# Diag64Cart.net
KiCad netlist of a schematic drawn in EAGLE
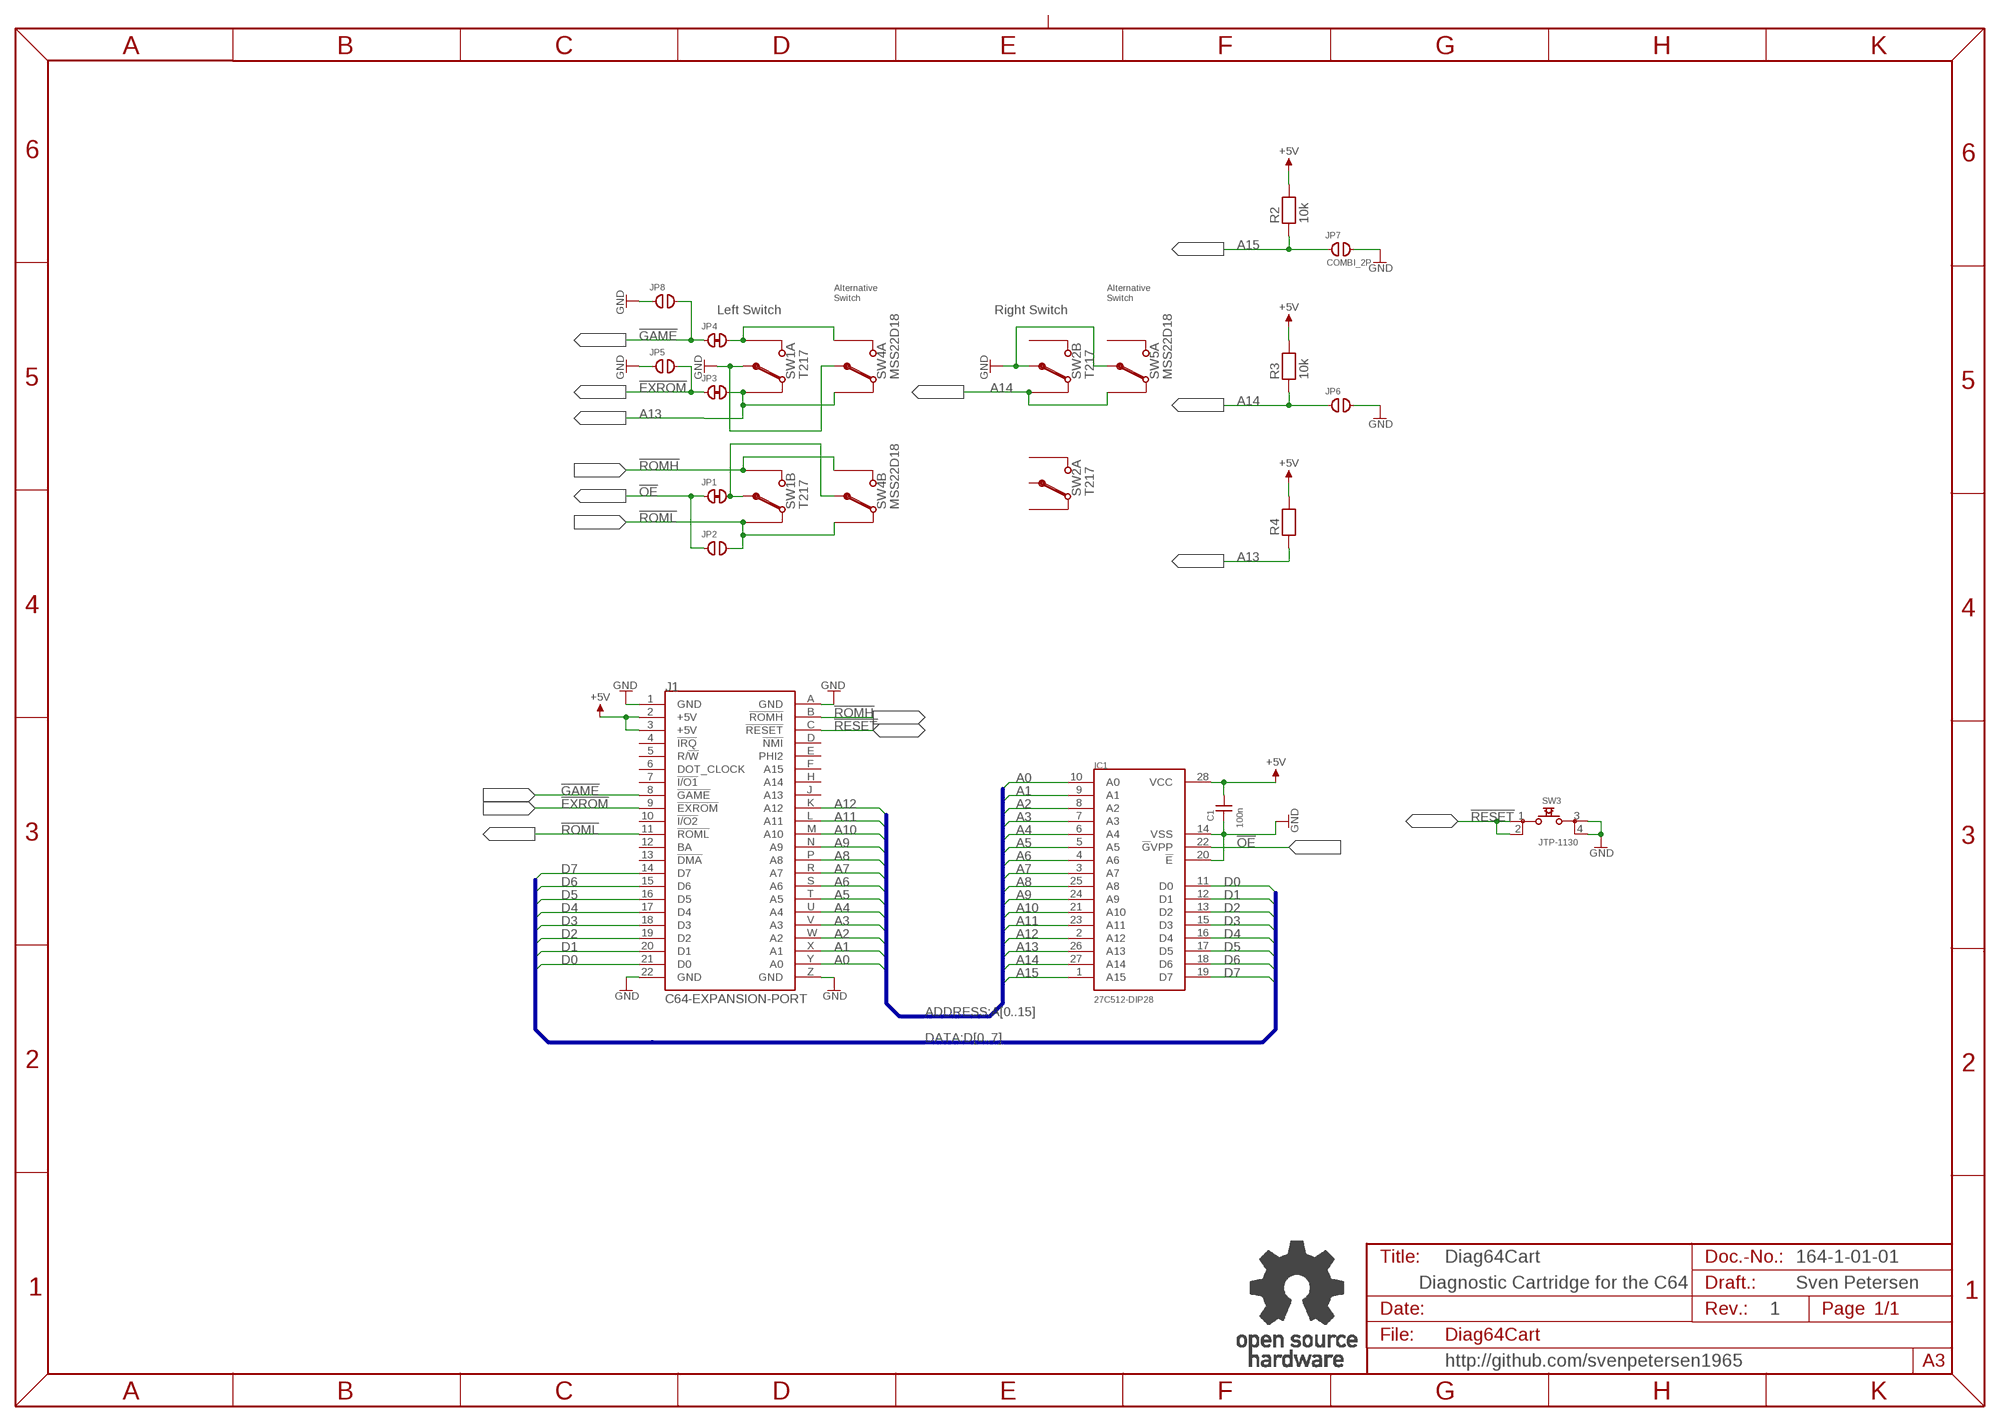
[diagram p0: schematic, sheet 1]

(export (version "E")
  (design (tool "Eeschema 10.0.6"))
  (components
    (comp (ref "C1")
      (value "100n")
      (footprint "eagle-import:C-2,5")
      (libsource (lib "eagle-import") (part "CAP01"))
    )
    (comp (ref "IC1")
      (value "27C512-DIP28")
      (footprint "eagle-import:DIL28-6")
      (libsource (lib "eagle-import") (part "M27C512-DIP28"))
    )
    (comp (ref "J1")
      (value "C64-EXPANSION-PORT")
      (footprint "eagle-import:EXPANSIO_SQ")
      (libsource (lib "eagle-import") (part "C64-EXPANSIONPNARROW"))
    )
    (comp (ref "JP1")
      (value "CLOSED")
      (footprint "eagle-import:CP_CL")
      (libsource (lib "eagle-import") (part "CLOSED"))
    )
    (comp (ref "JP2")
      (value "OPEN")
      (footprint "eagle-import:CP_OP")
      (libsource (lib "eagle-import") (part "OPEN"))
    )
    (comp (ref "JP3")
      (value "CLOSED")
      (footprint "eagle-import:CP_CL")
      (libsource (lib "eagle-import") (part "CLOSED"))
    )
    (comp (ref "JP4")
      (value "CLOSED")
      (footprint "eagle-import:CP_CL")
      (libsource (lib "eagle-import") (part "CLOSED"))
    )
    (comp (ref "JP5")
      (value "OPEN")
      (footprint "eagle-import:CP_OP")
      (libsource (lib "eagle-import") (part "OPEN"))
    )
    (comp (ref "JP6")
      (value "OPEN")
      (footprint "eagle-import:CP_OP")
      (libsource (lib "eagle-import") (part "OPEN"))
    )
    (comp (ref "JP7")
      (value "COMBI_2P")
      (footprint "eagle-import:COMBI-2P")
      (libsource (lib "eagle-import") (part "COMBI_2P"))
    )
    (comp (ref "JP8")
      (value "OPEN")
      (footprint "eagle-import:CP_OP")
      (libsource (lib "eagle-import") (part "OPEN"))
    )
    (comp (ref "R2")
      (value "10k")
      (footprint "eagle-import:R-10")
      (libsource (lib "eagle-import") (part "RES04"))
    )
    (comp (ref "R3")
      (value "10k")
      (footprint "eagle-import:R-10")
      (libsource (lib "eagle-import") (part "RES04"))
    )
    (comp (ref "R4")
      (value "10k")
      (footprint "eagle-import:R-10")
      (libsource (lib "eagle-import") (part "RES04"))
    )
    (comp (ref "SW1")
      (value "T217")
      (footprint "eagle-import:T217_SIDE")
      (libsource (lib "eagle-import") (part "T217"))
    )
    (comp (ref "SW2")
      (value "T217")
      (footprint "eagle-import:T217_SIDE")
      (libsource (lib "eagle-import") (part "T217"))
    )
    (comp (ref "SW3")
      (value "JTP-1130")
      (footprint "eagle-import:JTP-1130")
      (libsource (lib "eagle-import") (part "JTP-1130"))
    )
    (comp (ref "SW4")
      (value "MSS22D18")
      (footprint "eagle-import:DPDT_9MM")
      (libsource (lib "eagle-import") (part "DPDT_9MM"))
    )
    (comp (ref "SW5")
      (value "MSS22D18")
      (footprint "eagle-import:DPDT_9MM")
      (libsource (lib "eagle-import") (part "DPDT_9MM"))
    )
    (comp (ref "U$43")
      (value "OPEN_SOURCE_HW")
      (footprint "eagle-import:OPENHW")
      (libsource (lib "eagle-import") (part "OPEN_SOURCE_HW"))
    )
  )
  (nets
    (net (code "25") (name "+5V") (class "Default")
      (node (ref "C1") (pin "2") (pinfunction "2_2") (pintype "passive"))
      (node (ref "IC1") (pin "28") (pinfunction "VCC_28") (pintype "power_in"))
      (node (ref "J1") (pin "2") (pinfunction "+5V_2") (pintype "power_in"))
      (node (ref "J1") (pin "3") (pinfunction "+5V_3") (pintype "power_in"))
      (node (ref "R2") (pin "2") (pinfunction "2_2") (pintype "passive"))
      (node (ref "R3") (pin "2") (pinfunction "2_2") (pintype "passive"))
      (node (ref "R4") (pin "2") (pinfunction "2_2") (pintype "passive"))
    )
    (net (code "26") (name "/A0") (class "Default")
      (node (ref "IC1") (pin "10") (pinfunction "A0_10") (pintype "input"))
      (node (ref "J1") (pin "Y") (pinfunction "A0_Y") (pintype "bidirectional"))
    )
    (net (code "27") (name "/A1") (class "Default")
      (node (ref "IC1") (pin "9") (pinfunction "A1_9") (pintype "input"))
      (node (ref "J1") (pin "X") (pinfunction "A1_X") (pintype "bidirectional"))
    )
    (net (code "28") (name "/A2") (class "Default")
      (node (ref "IC1") (pin "8") (pinfunction "A2_8") (pintype "input"))
      (node (ref "J1") (pin "W") (pinfunction "A2_W") (pintype "bidirectional"))
    )
    (net (code "29") (name "/A3") (class "Default")
      (node (ref "IC1") (pin "7") (pinfunction "A3_7") (pintype "input"))
      (node (ref "J1") (pin "V") (pinfunction "A3_V") (pintype "bidirectional"))
    )
    (net (code "30") (name "/A4") (class "Default")
      (node (ref "IC1") (pin "6") (pinfunction "A4_6") (pintype "input"))
      (node (ref "J1") (pin "U") (pinfunction "A4_U") (pintype "bidirectional"))
    )
    (net (code "31") (name "/A5") (class "Default")
      (node (ref "IC1") (pin "5") (pinfunction "A5_5") (pintype "input"))
      (node (ref "J1") (pin "T") (pinfunction "A5_T") (pintype "bidirectional"))
    )
    (net (code "32") (name "/A6") (class "Default")
      (node (ref "IC1") (pin "4") (pinfunction "A6_4") (pintype "input"))
      (node (ref "J1") (pin "S") (pinfunction "A6_S") (pintype "bidirectional"))
    )
    (net (code "33") (name "/A7") (class "Default")
      (node (ref "IC1") (pin "3") (pinfunction "A7_3") (pintype "input"))
      (node (ref "J1") (pin "R") (pinfunction "A7_R") (pintype "bidirectional"))
    )
    (net (code "34") (name "/A8") (class "Default")
      (node (ref "IC1") (pin "25") (pinfunction "A8_25") (pintype "input"))
      (node (ref "J1") (pin "P") (pinfunction "A8_P") (pintype "bidirectional"))
    )
    (net (code "35") (name "/A9") (class "Default")
      (node (ref "IC1") (pin "24") (pinfunction "A9_24") (pintype "input"))
      (node (ref "J1") (pin "N") (pinfunction "A9_N") (pintype "bidirectional"))
    )
    (net (code "36") (name "/A10") (class "Default")
      (node (ref "IC1") (pin "21") (pinfunction "A10_21") (pintype "input"))
      (node (ref "J1") (pin "M") (pinfunction "A10_M") (pintype "bidirectional"))
    )
    (net (code "37") (name "/A11") (class "Default")
      (node (ref "IC1") (pin "23") (pinfunction "A11_23") (pintype "input"))
      (node (ref "J1") (pin "L") (pinfunction "A11_L") (pintype "bidirectional"))
    )
    (net (code "38") (name "/A12") (class "Default")
      (node (ref "IC1") (pin "2") (pinfunction "A12_2") (pintype "input"))
      (node (ref "J1") (pin "K") (pinfunction "A12_K") (pintype "bidirectional"))
    )
    (net (code "39") (name "/A13") (class "Default")
      (node (ref "IC1") (pin "26") (pinfunction "A13_26") (pintype "input"))
      (node (ref "JP3") (pin "2") (pinfunction "2_2") (pintype "passive"))
      (node (ref "R4") (pin "1") (pinfunction "1_1") (pintype "passive"))
      (node (ref "SW1") (pin "DWN1") (pinfunction "DWN_DWN1") (pintype "bidirectional"))
      (node (ref "SW4") (pin "3") (pinfunction "DWN_3") (pintype "bidirectional"))
    )
    (net (code "40") (name "/A14") (class "Default")
      (node (ref "IC1") (pin "27") (pinfunction "A14_27") (pintype "input"))
      (node (ref "JP6") (pin "1") (pinfunction "1_1") (pintype "passive"))
      (node (ref "R3") (pin "1") (pinfunction "1_1") (pintype "passive"))
      (node (ref "SW2") (pin "DWN2") (pinfunction "DWN_DWN2") (pintype "bidirectional"))
      (node (ref "SW5") (pin "3") (pinfunction "DWN_3") (pintype "bidirectional"))
    )
    (net (code "41") (name "/A15") (class "Default")
      (node (ref "IC1") (pin "1") (pinfunction "A15_1") (pintype "input"))
      (node (ref "JP7") (pin "1") (pinfunction "1_1") (pintype "passive"))
      (node (ref "R2") (pin "1") (pinfunction "1_1") (pintype "passive"))
    )
    (net (code "43") (name "/D0") (class "Default")
      (node (ref "IC1") (pin "11") (pinfunction "D0_11") (pintype "bidirectional"))
      (node (ref "J1") (pin "21") (pinfunction "D0_21") (pintype "bidirectional"))
    )
    (net (code "44") (name "/D1") (class "Default")
      (node (ref "IC1") (pin "12") (pinfunction "D1_12") (pintype "bidirectional"))
      (node (ref "J1") (pin "20") (pinfunction "D1_20") (pintype "bidirectional"))
    )
    (net (code "45") (name "/D2") (class "Default")
      (node (ref "IC1") (pin "13") (pinfunction "D2_13") (pintype "bidirectional"))
      (node (ref "J1") (pin "19") (pinfunction "D2_19") (pintype "bidirectional"))
    )
    (net (code "46") (name "/D3") (class "Default")
      (node (ref "IC1") (pin "15") (pinfunction "D3_15") (pintype "bidirectional"))
      (node (ref "J1") (pin "18") (pinfunction "D3_18") (pintype "bidirectional"))
    )
    (net (code "47") (name "/D4") (class "Default")
      (node (ref "IC1") (pin "16") (pinfunction "D4_16") (pintype "bidirectional"))
      (node (ref "J1") (pin "17") (pinfunction "D4_17") (pintype "bidirectional"))
    )
    (net (code "48") (name "/D5") (class "Default")
      (node (ref "IC1") (pin "17") (pinfunction "D5_17") (pintype "bidirectional"))
      (node (ref "J1") (pin "16") (pinfunction "D5_16") (pintype "bidirectional"))
    )
    (net (code "49") (name "/D6") (class "Default")
      (node (ref "IC1") (pin "18") (pinfunction "D6_18") (pintype "bidirectional"))
      (node (ref "J1") (pin "15") (pinfunction "D6_15") (pintype "bidirectional"))
    )
    (net (code "50") (name "/D7") (class "Default")
      (node (ref "IC1") (pin "19") (pinfunction "D7_19") (pintype "bidirectional"))
      (node (ref "J1") (pin "14") (pinfunction "D7_14") (pintype "bidirectional"))
    )
    (net (code "52") (name "/~{EXROM}") (class "Default")
      (node (ref "J1") (pin "9") (pinfunction "~{EXROM}_9") (pintype "input"))
      (node (ref "JP3") (pin "1") (pinfunction "1_1") (pintype "passive"))
      (node (ref "JP5") (pin "2") (pinfunction "2_2") (pintype "passive"))
    )
    (net (code "53") (name "/~{GAME}") (class "Default")
      (node (ref "J1") (pin "8") (pinfunction "~{GAME}_8") (pintype "input"))
      (node (ref "JP4") (pin "1") (pinfunction "1_1") (pintype "passive"))
      (node (ref "JP8") (pin "2") (pinfunction "2_2") (pintype "passive"))
    )
    (net (code "54") (name "/~{OE}") (class "Default")
      (node (ref "IC1") (pin "22") (pinfunction "~{G}VPP_22") (pintype "input"))
      (node (ref "JP1") (pin "1") (pinfunction "1_1") (pintype "passive"))
      (node (ref "JP2") (pin "1") (pinfunction "1_1") (pintype "passive"))
    )
    (net (code "55") (name "/~{RESET}") (class "Default")
      (node (ref "J1") (pin "C") (pinfunction "~{RESET}_C") (pintype "open_collector"))
      (node (ref "SW3") (pin "1") (pinfunction "1_1") (pintype "passive"))
      (node (ref "SW3") (pin "2") (pinfunction "2_2") (pintype "passive"))
    )
    (net (code "56") (name "/~{ROMH}") (class "Default")
      (node (ref "J1") (pin "B") (pinfunction "~{ROMH}_B") (pintype "output"))
      (node (ref "SW1") (pin "UP2") (pinfunction "UP_UP2") (pintype "bidirectional"))
      (node (ref "SW4") (pin "6") (pinfunction "UP_6") (pintype "bidirectional"))
    )
    (net (code "57") (name "/~{ROML}") (class "Default")
      (node (ref "J1") (pin "11") (pinfunction "~{ROML}_11") (pintype "output"))
      (node (ref "JP2") (pin "2") (pinfunction "2_2") (pintype "passive"))
      (node (ref "SW1") (pin "DWN2") (pinfunction "DWN_DWN2") (pintype "bidirectional"))
      (node (ref "SW4") (pin "4") (pinfunction "DWN_4") (pintype "bidirectional"))
    )
    (net (code "58") (name "GND") (class "Default")
      (node (ref "C1") (pin "1") (pinfunction "1_1") (pintype "passive"))
      (node (ref "IC1") (pin "14") (pinfunction "VSS_14") (pintype "power_in"))
      (node (ref "IC1") (pin "20") (pinfunction "~{E}_20") (pintype "input"))
      (node (ref "J1") (pin "1") (pinfunction "GND_1") (pintype "power_in"))
      (node (ref "J1") (pin "22") (pinfunction "GND_22") (pintype "power_in"))
      (node (ref "J1") (pin "A") (pinfunction "GND_A") (pintype "power_in"))
      (node (ref "J1") (pin "Z") (pinfunction "GND_Z") (pintype "power_in"))
      (node (ref "JP5") (pin "1") (pinfunction "1_1") (pintype "passive"))
      (node (ref "JP6") (pin "2") (pinfunction "2_2") (pintype "passive"))
      (node (ref "JP7") (pin "2") (pinfunction "2_2") (pintype "passive"))
      (node (ref "JP8") (pin "1") (pinfunction "1_1") (pintype "passive"))
      (node (ref "SW1") (pin "COM1") (pinfunction "COM_COM1") (pintype "bidirectional"))
      (node (ref "SW2") (pin "COM2") (pinfunction "COM_COM2") (pintype "bidirectional"))
      (node (ref "SW3") (pin "3") (pinfunction "3_3") (pintype "passive"))
      (node (ref "SW3") (pin "4") (pinfunction "4_4") (pintype "passive"))
      (node (ref "SW4") (pin "2") (pinfunction "COM_2") (pintype "bidirectional"))
      (node (ref "SW5") (pin "2") (pinfunction "COM_2") (pintype "bidirectional"))
    )
    (net (code "59") (name "Net-(SW1A-UP)") (class "Default")
      (node (ref "JP4") (pin "2") (pinfunction "2_2") (pintype "passive"))
      (node (ref "SW1") (pin "UP1") (pinfunction "UP_UP1") (pintype "bidirectional"))
      (node (ref "SW4") (pin "1") (pinfunction "UP_1") (pintype "bidirectional"))
    )
    (net (code "60") (name "Net-(SW1B-COM)") (class "Default")
      (node (ref "JP1") (pin "2") (pinfunction "2_2") (pintype "passive"))
      (node (ref "SW1") (pin "COM2") (pinfunction "COM_COM2") (pintype "bidirectional"))
      (node (ref "SW4") (pin "5") (pinfunction "COM_5") (pintype "bidirectional"))
    )
    (net (code "61") (name "unconnected-(J1-A13-PadJ)") (class "Default")
      (node (ref "J1") (pin "J") (pinfunction "A13_J") (pintype "bidirectional"))
    )
    (net (code "62") (name "unconnected-(J1-A14-PadH)") (class "Default")
      (node (ref "J1") (pin "H") (pinfunction "A14_H") (pintype "bidirectional"))
    )
    (net (code "63") (name "unconnected-(J1-A15-PadF)") (class "Default")
      (node (ref "J1") (pin "F") (pinfunction "A15_F") (pintype "bidirectional"))
    )
    (net (code "64") (name "unconnected-(J1-BA-Pad12)") (class "Default")
      (node (ref "J1") (pin "12") (pinfunction "BA_12") (pintype "output"))
    )
    (net (code "65") (name "unconnected-(J1-DOT_CLOCK-Pad6)") (class "Default")
      (node (ref "J1") (pin "6") (pinfunction "DOT_CLOCK_6") (pintype "output"))
    )
    (net (code "66") (name "unconnected-(J1-PHI2-PadE)") (class "Default")
      (node (ref "J1") (pin "E") (pinfunction "PHI2_E") (pintype "output"))
    )
    (net (code "67") (name "unconnected-(J1-R{slash}~{W}-Pad5)") (class "Default")
      (node (ref "J1") (pin "5") (pinfunction "R/~{W}_5") (pintype "output"))
    )
    (net (code "68") (name "unconnected-(J1-~{DMA}-Pad13)") (class "Default")
      (node (ref "J1") (pin "13") (pinfunction "~{DMA}_13") (pintype "input"))
    )
    (net (code "69") (name "unconnected-(J1-~{IRQ}-Pad4)") (class "Default")
      (node (ref "J1") (pin "4") (pinfunction "~{IRQ}_4") (pintype "input"))
    )
    (net (code "70") (name "unconnected-(J1-~{I{slash}O1}-Pad7)") (class "Default")
      (node (ref "J1") (pin "7") (pinfunction "~{I/O1}_7") (pintype "output"))
    )
    (net (code "71") (name "unconnected-(J1-~{I{slash}O2}-Pad10)") (class "Default")
      (node (ref "J1") (pin "10") (pinfunction "~{I/O2}_10") (pintype "output"))
    )
    (net (code "72") (name "unconnected-(J1-~{NMI}-PadD)") (class "Default")
      (node (ref "J1") (pin "D") (pinfunction "~{NMI}_D") (pintype "input"))
    )
    (net (code "73") (name "unconnected-(SW2A-COM-PadCOM1)") (class "Default")
      (node (ref "SW2") (pin "COM1") (pinfunction "COM_COM1") (pintype "bidirectional"))
    )
    (net (code "74") (name "unconnected-(SW2A-DWN-PadDWN1)") (class "Default")
      (node (ref "SW2") (pin "DWN1") (pinfunction "DWN_DWN1") (pintype "bidirectional"))
    )
    (net (code "75") (name "unconnected-(SW2A-UP-PadUP1)") (class "Default")
      (node (ref "SW2") (pin "UP1") (pinfunction "UP_UP1") (pintype "bidirectional"))
    )
    (net (code "76") (name "unconnected-(SW2B-UP-PadUP2)") (class "Default")
      (node (ref "SW2") (pin "UP2") (pinfunction "UP_UP2") (pintype "bidirectional"))
    )
    (net (code "77") (name "unconnected-(SW5A-UP-Pad1)") (class "Default")
      (node (ref "SW5") (pin "1") (pinfunction "UP_1") (pintype "bidirectional"))
    )
  )
)
